# EXE_IO.net
KiCad netlist of a schematic drawn in Altium Designer
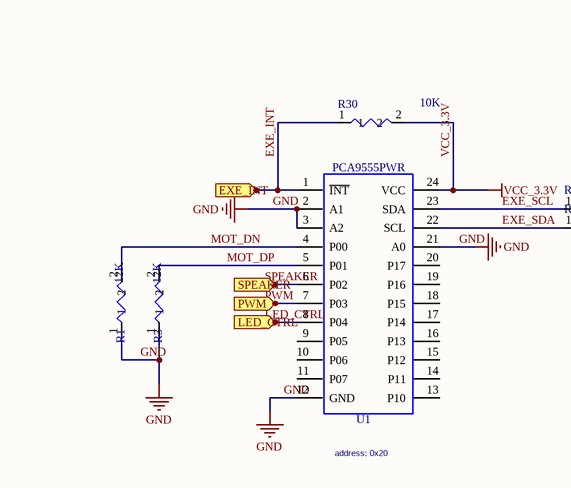
[diagram p0: EXE_IO.SchDoc, top left]
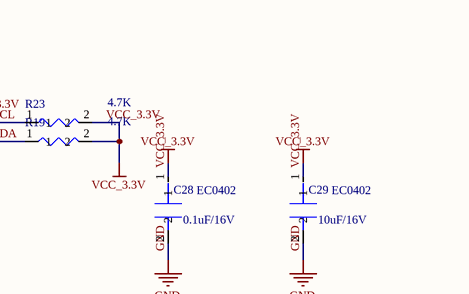
[diagram p1: EXE_IO.SchDoc, top right]
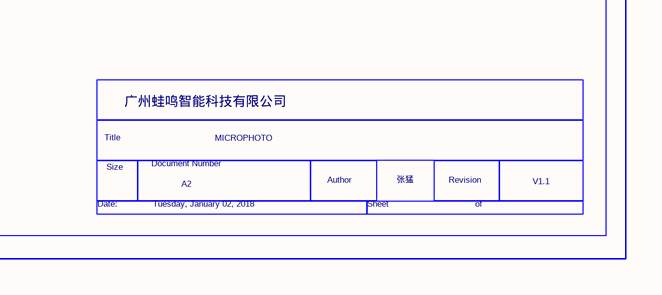
[diagram p2: EXE_IO.SchDoc, bottom right]

(export (version "E")
  (design (tool "Eeschema 10.0.6"))
  (components
    (comp (ref "C28")
      (value "EC0402")
      (fields (field (name "ALTIUM_VALUE") "0.1uF/16V"))
      (libsource (lib "*") (part "EC0402"))
    )
    (comp (ref "C29")
      (value "EC0402")
      (fields (field (name "ALTIUM_VALUE") "10uF/16V"))
      (libsource (lib "*") (part "EC0402"))
    )
    (comp (ref "R1")
      (value "12K")
      (fields (field (name "Comment") "ER0402"))
      (libsource (lib "*") (part "ER0402"))
    )
    (comp (ref "R3")
      (value "12K")
      (fields (field (name "Comment") "ER0402"))
      (libsource (lib "*") (part "ER0402"))
    )
    (comp (ref "R19")
      (value "4.7K")
      (fields (field (name "Comment") "ER0402"))
      (libsource (lib "*") (part "ER0402"))
    )
    (comp (ref "R23")
      (value "4.7K")
      (fields (field (name "Comment") "ER0402"))
      (libsource (lib "*") (part "ER0402"))
    )
    (comp (ref "R30")
      (value "10K")
      (fields (field (name "Comment") "ER0402"))
      (libsource (lib "*") (part "ER0402"))
    )
    (comp (ref "U1") (value "PCA9555PWR") (libsource (lib "*") (part "PCA9555PWR")))
  )
  (nets
    (net (code "1") (name "/EXE_INT") (class "Default")
      (node (ref "R30") (pin "1") (pinfunction "1_1") (pintype "passive"))
      (node (ref "U1") (pin "1") (pinfunction "~{INT}_1") (pintype "passive"))
    )
    (net (code "2") (name "/EXE_SCL") (class "Default")
      (node (ref "R23") (pin "1") (pinfunction "1_1") (pintype "passive"))
      (node (ref "U1") (pin "23") (pinfunction "SDA_23") (pintype "passive"))
    )
    (net (code "3") (name "/EXE_SDA") (class "Default")
      (node (ref "R19") (pin "1") (pinfunction "1_1") (pintype "passive"))
      (node (ref "U1") (pin "22") (pinfunction "SCL_22") (pintype "passive"))
    )
    (net (code "4") (name "/LED_CTRL") (class "Default")
      (node (ref "U1") (pin "8") (pinfunction "P04_8") (pintype "passive"))
    )
    (net (code "5") (name "/MOT_DN") (class "Default")
      (node (ref "R1") (pin "2") (pinfunction "2_2") (pintype "passive"))
      (node (ref "U1") (pin "4") (pinfunction "P00_4") (pintype "passive"))
    )
    (net (code "6") (name "/MOT_DP") (class "Default")
      (node (ref "R3") (pin "2") (pinfunction "2_2") (pintype "passive"))
      (node (ref "U1") (pin "5") (pinfunction "P01_5") (pintype "passive"))
    )
    (net (code "7") (name "/PWM") (class "Default")
      (node (ref "U1") (pin "7") (pinfunction "P03_7") (pintype "passive"))
    )
    (net (code "8") (name "/SPEAKER") (class "Default")
      (node (ref "U1") (pin "6") (pinfunction "P02_6") (pintype "passive"))
    )
    (net (code "9") (name "GND") (class "Default")
      (node (ref "C28") (pin "2") (pinfunction "2_2") (pintype "passive"))
      (node (ref "C29") (pin "2") (pinfunction "2_2") (pintype "passive"))
      (node (ref "R1") (pin "1") (pinfunction "1_1") (pintype "passive"))
      (node (ref "R3") (pin "1") (pinfunction "1_1") (pintype "passive"))
      (node (ref "U1") (pin "12") (pinfunction "GND_12") (pintype "passive"))
      (node (ref "U1") (pin "2") (pinfunction "A1_2") (pintype "passive"))
      (node (ref "U1") (pin "21") (pinfunction "A0_21") (pintype "passive"))
      (node (ref "U1") (pin "3") (pinfunction "A2_3") (pintype "passive"))
    )
    (net (code "10") (name "VCC_3.3V") (class "Default")
      (node (ref "C28") (pin "1") (pinfunction "1_1") (pintype "passive"))
      (node (ref "C29") (pin "1") (pinfunction "1_1") (pintype "passive"))
      (node (ref "R19") (pin "2") (pinfunction "2_2") (pintype "passive"))
      (node (ref "R23") (pin "2") (pinfunction "2_2") (pintype "passive"))
      (node (ref "R30") (pin "2") (pinfunction "2_2") (pintype "passive"))
      (node (ref "U1") (pin "24") (pinfunction "VCC_24") (pintype "passive"))
    )
    (net (code "11") (name "unconnected-(U1-P05-Pad9)") (class "Default")
      (node (ref "U1") (pin "9") (pinfunction "P05_9") (pintype "passive"))
    )
    (net (code "12") (name "unconnected-(U1-P06-Pad10)") (class "Default")
      (node (ref "U1") (pin "10") (pinfunction "P06_10") (pintype "passive"))
    )
    (net (code "13") (name "unconnected-(U1-P07-Pad11)") (class "Default")
      (node (ref "U1") (pin "11") (pinfunction "P07_11") (pintype "passive"))
    )
    (net (code "14") (name "unconnected-(U1-P10-Pad13)") (class "Default")
      (node (ref "U1") (pin "13") (pinfunction "P10_13") (pintype "passive"))
    )
    (net (code "15") (name "unconnected-(U1-P11-Pad14)") (class "Default")
      (node (ref "U1") (pin "14") (pinfunction "P11_14") (pintype "passive"))
    )
    (net (code "16") (name "unconnected-(U1-P12-Pad15)") (class "Default")
      (node (ref "U1") (pin "15") (pinfunction "P12_15") (pintype "passive"))
    )
    (net (code "17") (name "unconnected-(U1-P13-Pad16)") (class "Default")
      (node (ref "U1") (pin "16") (pinfunction "P13_16") (pintype "passive"))
    )
    (net (code "18") (name "unconnected-(U1-P14-Pad17)") (class "Default")
      (node (ref "U1") (pin "17") (pinfunction "P14_17") (pintype "passive"))
    )
    (net (code "19") (name "unconnected-(U1-P15-Pad18)") (class "Default")
      (node (ref "U1") (pin "18") (pinfunction "P15_18") (pintype "passive"))
    )
    (net (code "20") (name "unconnected-(U1-P16-Pad19)") (class "Default")
      (node (ref "U1") (pin "19") (pinfunction "P16_19") (pintype "passive"))
    )
    (net (code "21") (name "unconnected-(U1-P17-Pad20)") (class "Default")
      (node (ref "U1") (pin "20") (pinfunction "P17_20") (pintype "passive"))
    )
  )
)
